# atmel-atmega328p-led-strip-controller.net
KiCad netlist of a schematic drawn in EAGLE
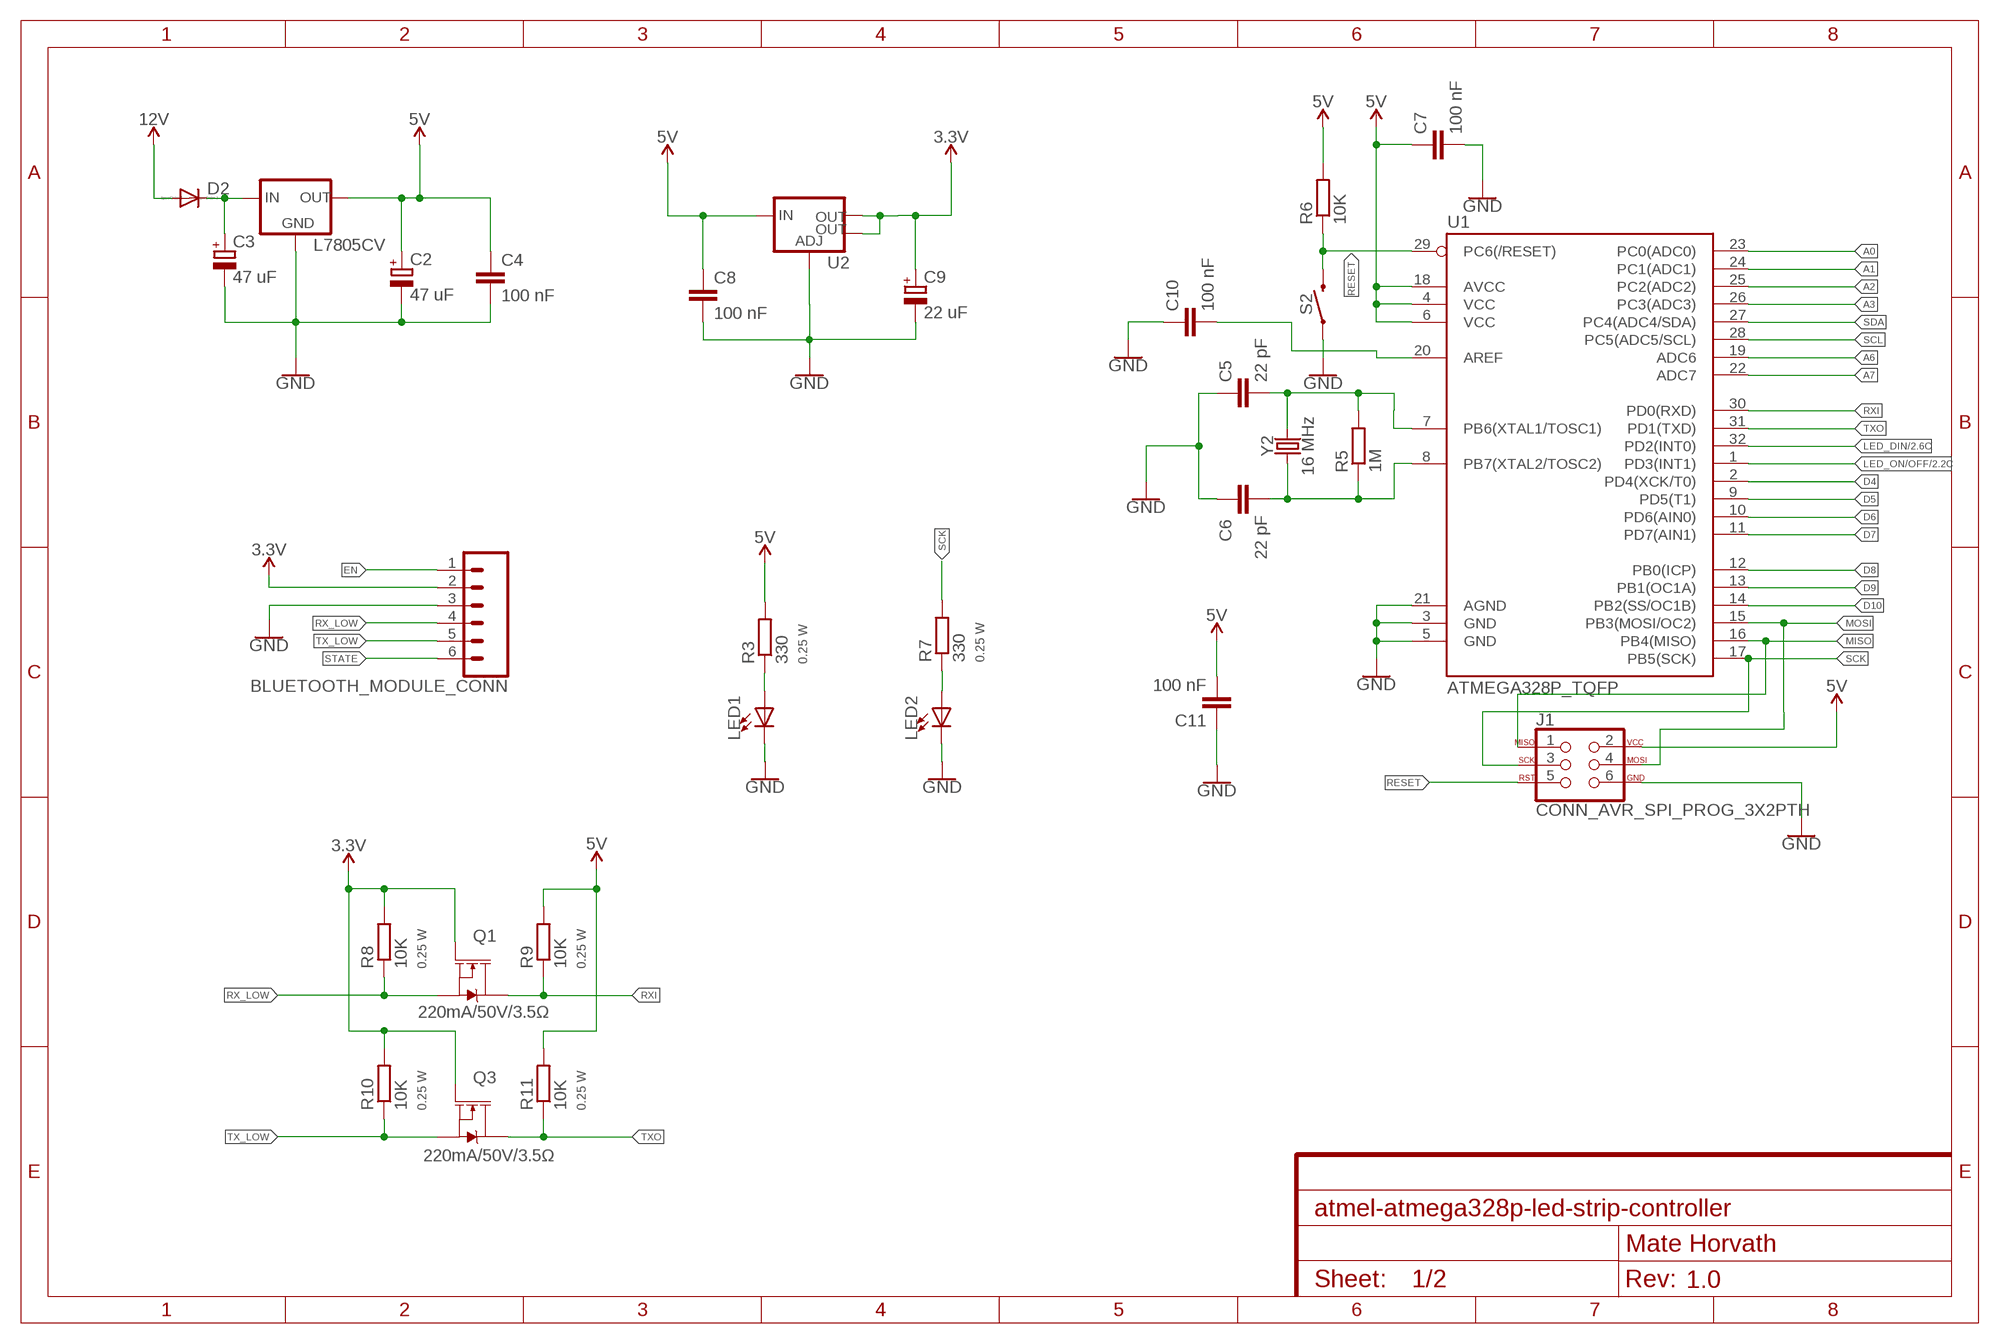
[diagram p0: schematic, sheet 1]
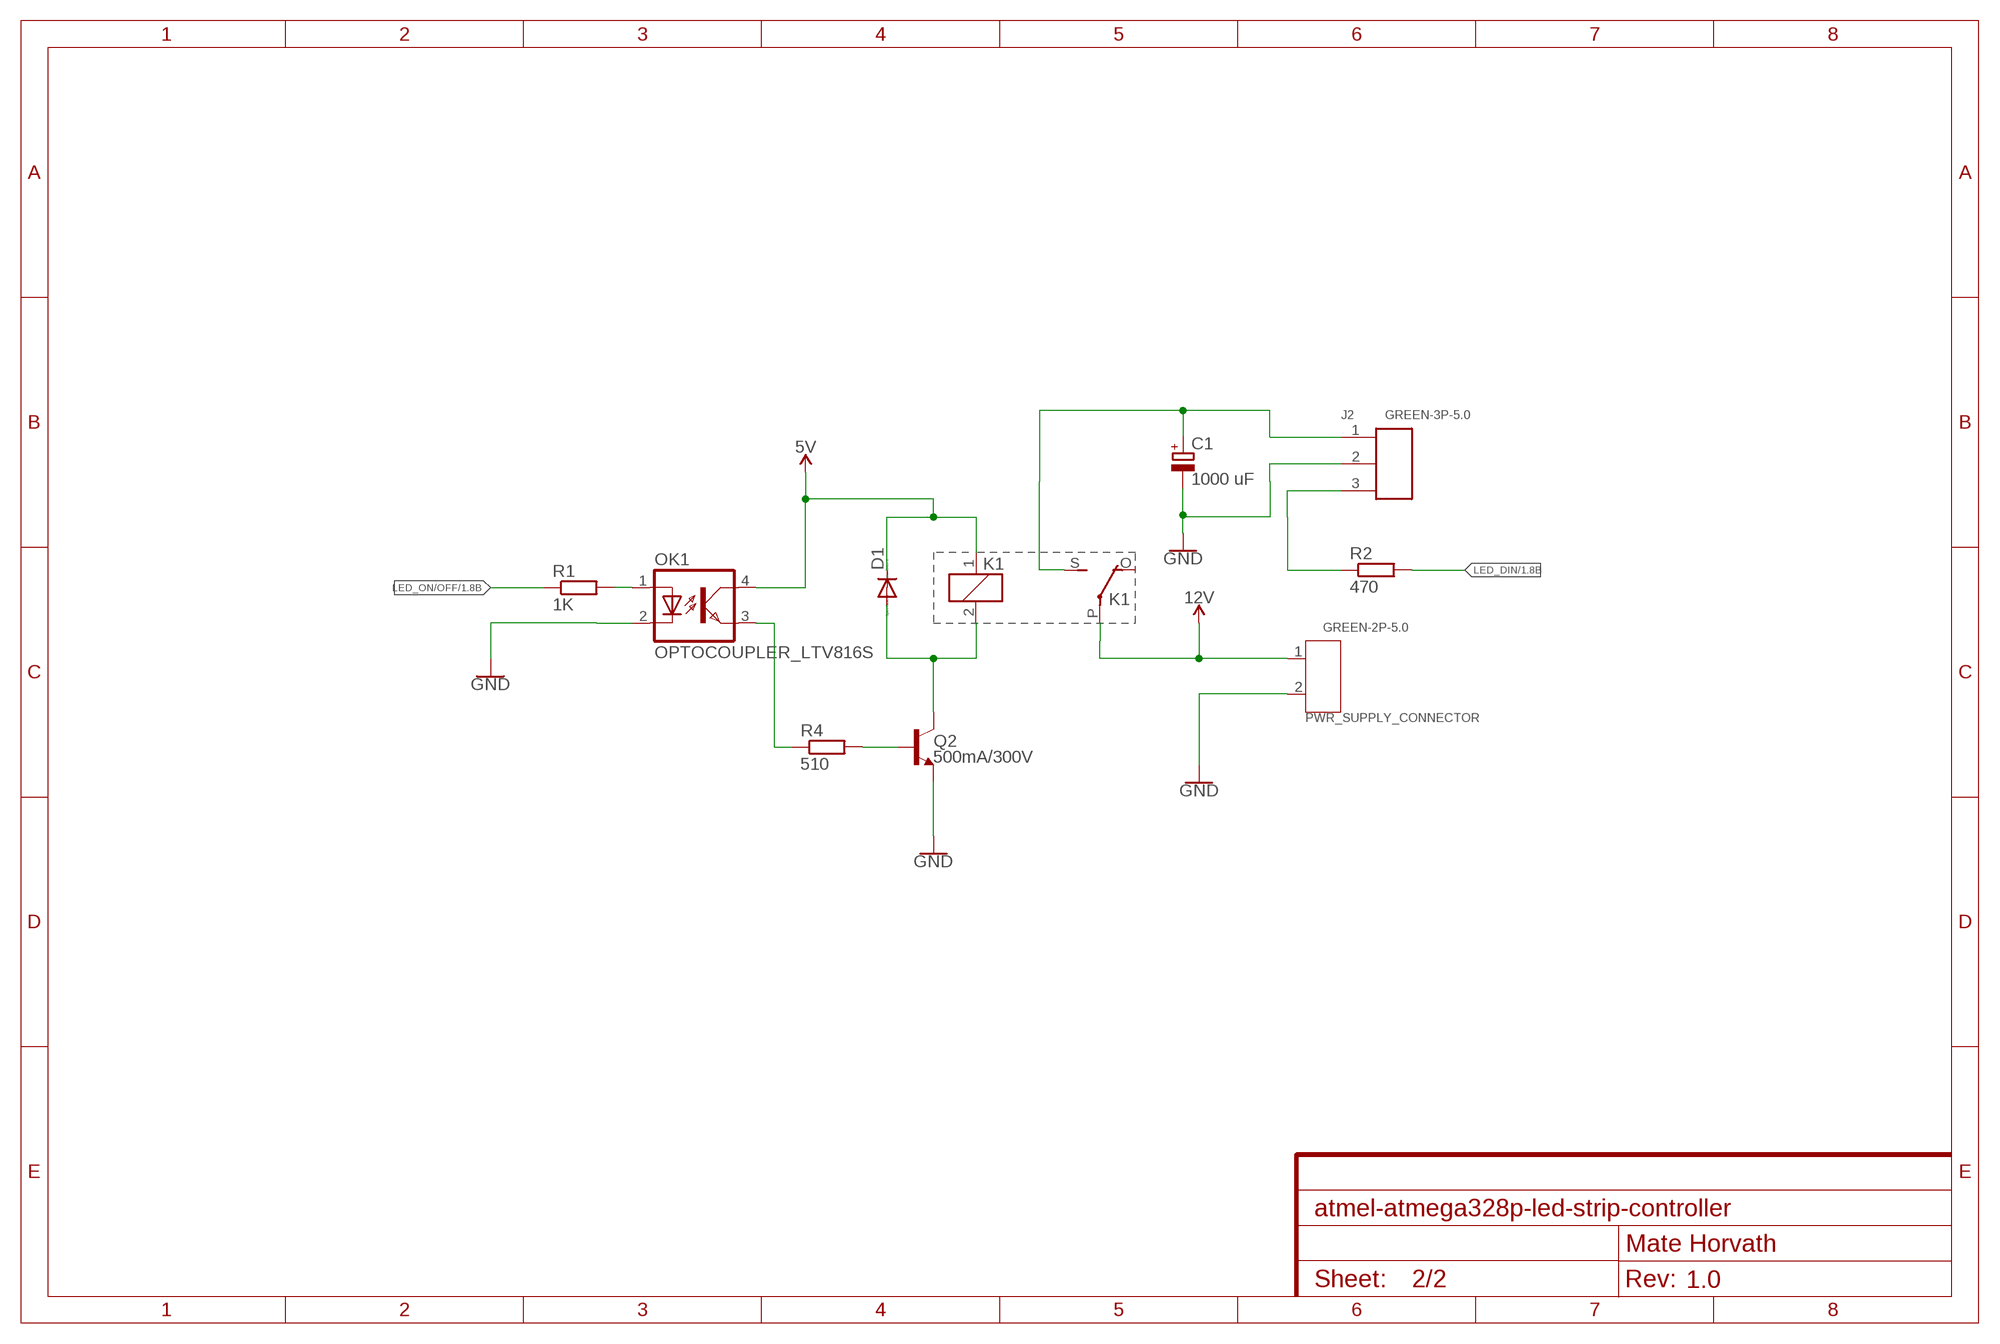
[diagram p1: schematic, sheet 2]

(export (version "E")
  (design (tool "Eeschema 10.0.6"))
  (components
    (comp (ref "C1")
      (value "1000 uF")
      (footprint "eagle-import:E5-13")
      (libsource (lib "eagle-import") (part "CAPACITOR_POLARIZEDE5-13"))
    )
    (comp (ref "D1")
      (value "DIODED-10")
      (footprint "eagle-import:D-10")
      (libsource (lib "eagle-import") (part "DIODED-10"))
    )
    (comp (ref "J2")
      (value "GREEN-3P-5.0")
      (footprint "eagle-import:H3-5.0-15.5X8.0MM")
      (libsource (lib "eagle-import") (part "SCREW-TERMINAL-GREEN(3P-5.0)"))
    )
    (comp (ref "K1")
      (value "RELAY_ZF112")
      (footprint "eagle-import:ZF112")
      (libsource (lib "eagle-import") (part "RELAY_ZF112"))
    )
    (comp (ref "OK1")
      (value "OPTOCOUPLER_LTV816S")
      (footprint "eagle-import:DIL4-SMD")
      (libsource (lib "eagle-import") (part "OPTOCOUPLER_LTV816S"))
    )
    (comp (ref "PWR_SUPPLY_CONNECTOR")
      (value "GREEN-2P-5.0")
      (footprint "eagle-import:H2-5.0-10.5X8.0MM")
      (libsource (lib "eagle-import") (part "SCREW-TERMINAL-GREEN(2P-5.0)"))
    )
    (comp (ref "Q2")
      (value "500mA/300V")
      (footprint "eagle-import:SOT23-3")
      (libsource (lib "eagle-import") (part "TRAN_NPN-MMBTA42"))
    )
    (comp (ref "R1")
      (value "1K")
      (footprint "eagle-import:R1206")
      (fields (field (name "POWER") "0.25 W"))
      (libsource (lib "eagle-import") (part "RESISTORR1206"))
    )
    (comp (ref "R2")
      (value "470")
      (footprint "eagle-import:R1206")
      (fields (field (name "POWER") "0.25 W"))
      (libsource (lib "eagle-import") (part "RESISTORR1206"))
    )
    (comp (ref "R4")
      (value "510")
      (footprint "eagle-import:R1206")
      (fields (field (name "POWER") "0.25 W"))
      (libsource (lib "eagle-import") (part "RESISTORR1206"))
    )
    (comp (ref "BLUETOOTH_MODULE_CONN")
      (value "CONN_06SILK_FEMALE_PTH")
      (footprint "eagle-import:1X06")
      (libsource (lib "eagle-import") (part "CONN_06SILK_FEMALE_PTH"))
    )
    (comp (ref "C2")
      (value "47 uF")
      (footprint "eagle-import:E2,5-5")
      (libsource (lib "eagle-import") (part "CAPACITOR_POLARIZEDE2.5-5"))
    )
    (comp (ref "C3")
      (value "47 uF")
      (footprint "eagle-import:E2,5-5")
      (libsource (lib "eagle-import") (part "CAPACITOR_POLARIZEDE2.5-5"))
    )
    (comp (ref "C4")
      (value "100 nF")
      (footprint "eagle-import:C1206I-C3216M")
      (libsource (lib "eagle-import") (part "CAPACITOR_1C1206"))
    )
    (comp (ref "C5")
      (value "22 pF")
      (footprint "eagle-import:C1206I-C3216M")
      (libsource (lib "eagle-import") (part "CAPACITOR_1C1206"))
    )
    (comp (ref "C6")
      (value "22 pF")
      (footprint "eagle-import:C1206I-C3216M")
      (libsource (lib "eagle-import") (part "CAPACITOR_1C1206"))
    )
    (comp (ref "C7")
      (value "100 nF")
      (footprint "eagle-import:C1206I-C3216M")
      (libsource (lib "eagle-import") (part "CAPACITOR_1C1206"))
    )
    (comp (ref "C8")
      (value "100 nF")
      (footprint "eagle-import:C1206I-C3216M")
      (libsource (lib "eagle-import") (part "CAPACITOR_1C1206"))
    )
    (comp (ref "C9")
      (value "22 uF")
      (footprint "eagle-import:153CLV-0505")
      (libsource (lib "eagle-import") (part "CAPACITOR_POLARIZED153CLV-0505"))
    )
    (comp (ref "C10")
      (value "100 nF")
      (footprint "eagle-import:C1206I-C3216M")
      (libsource (lib "eagle-import") (part "CAPACITOR_1C1206"))
    )
    (comp (ref "C11")
      (value "100 nF")
      (footprint "eagle-import:C1206I-C3216M")
      (libsource (lib "eagle-import") (part "CAPACITOR_1C1206"))
    )
    (comp (ref "D2")
      (value "DIODED-10")
      (footprint "eagle-import:D-10")
      (libsource (lib "eagle-import") (part "DIODED-10"))
    )
    (comp (ref "J1")
      (value "CONN_AVR_SPI_PROG_3X2PTH")
      (footprint "eagle-import:2X3_S")
      (libsource (lib "eagle-import") (part "CONN_AVR_SPI_PROG_3X2PTH"))
    )
    (comp (ref "L7805CV")
      (value "V_REG_78XX_STANDING")
      (footprint "eagle-import:78XXS")
      (libsource (lib "eagle-import") (part "V_REG_78XX_STANDING"))
    )
    (comp (ref "LED1")
      (value "LEDCHIPLED_1206_G")
      (footprint "eagle-import:LED_1206_G")
      (libsource (lib "eagle-import") (part "LEDCHIPLED_1206_G"))
    )
    (comp (ref "LED2")
      (value "LEDCHIPLED_1206_G")
      (footprint "eagle-import:LED_1206_G")
      (libsource (lib "eagle-import") (part "LEDCHIPLED_1206_G"))
    )
    (comp (ref "Q1")
      (value "220mA/50V/3.5Ω")
      (footprint "eagle-import:SOT23-3")
      (libsource (lib "eagle-import") (part "MOSFET_NCHN_SMD-BSS138"))
    )
    (comp (ref "Q3")
      (value "220mA/50V/3.5Ω")
      (footprint "eagle-import:SOT23-3")
      (libsource (lib "eagle-import") (part "MOSFET_NCHN_SMD-BSS138"))
    )
    (comp (ref "R3")
      (value "330")
      (footprint "eagle-import:R1206")
      (fields (field (name "POWER") "0.25 W"))
      (libsource (lib "eagle-import") (part "RESISTORR1206"))
    )
    (comp (ref "R5")
      (value "1M")
      (footprint "eagle-import:R1206")
      (fields (field (name "POWER") "0.25 W"))
      (libsource (lib "eagle-import") (part "RESISTORR1206"))
    )
    (comp (ref "R6")
      (value "10K")
      (footprint "eagle-import:R1206")
      (fields (field (name "POWER") "0.25 W"))
      (libsource (lib "eagle-import") (part "RESISTORR1206"))
    )
    (comp (ref "R7")
      (value "330")
      (footprint "eagle-import:R1206")
      (fields (field (name "POWER") "0.25 W"))
      (libsource (lib "eagle-import") (part "RESISTORR1206"))
    )
    (comp (ref "R8")
      (value "10K")
      (footprint "eagle-import:R1206")
      (fields (field (name "POWER") "0.25 W"))
      (libsource (lib "eagle-import") (part "RESISTORR1206"))
    )
    (comp (ref "R9")
      (value "10K")
      (footprint "eagle-import:R1206")
      (fields (field (name "POWER") "0.25 W"))
      (libsource (lib "eagle-import") (part "RESISTORR1206"))
    )
    (comp (ref "R10")
      (value "10K")
      (footprint "eagle-import:R1206")
      (fields (field (name "POWER") "0.25 W"))
      (libsource (lib "eagle-import") (part "RESISTORR1206"))
    )
    (comp (ref "R11")
      (value "10K")
      (footprint "eagle-import:R1206")
      (fields (field (name "POWER") "0.25 W"))
      (libsource (lib "eagle-import") (part "RESISTORR1206"))
    )
    (comp (ref "S2")
      (value "INPUT_MOMENTARY_SWITCH_SPST-SMD-5.2MM")
      (footprint "eagle-import:TACTILE_SWITCH_SMD_5.2MM")
      (libsource (lib "eagle-import") (part "INPUT_MOMENTARY_SWITCH_SPST-SMD-5.2MM"))
    )
    (comp (ref "U1")
      (value "ATMEGA328P_TQFP")
      (footprint "eagle-import:TQFP32-08")
      (libsource (lib "eagle-import") (part "MCU_ATMEGA328P_TQFP"))
    )
    (comp (ref "U2")
      (value "V_REG_LM1117SOT223")
      (footprint "eagle-import:SOT223")
      (libsource (lib "eagle-import") (part "V_REG_LM1117SOT223"))
    )
    (comp (ref "Y2")
      (value "16 MHz")
      (footprint "eagle-import:CRYSTAL-SMD-3.2X2.5MM")
      (libsource (lib "eagle-import") (part "CRYSTALSMD-3.2X2.5"))
    )
  )
  (nets
    (net (code "1") (name "3.3V") (class "Default")
      (node (ref "BLUETOOTH_MODULE_CONN") (pin "2") (pinfunction "2_2") (pintype "passive"))
      (node (ref "C9") (pin "+") (pinfunction "+_+") (pintype "passive"))
      (node (ref "Q1") (pin "1") (pinfunction "G_1") (pintype "bidirectional"))
      (node (ref "Q3") (pin "1") (pinfunction "G_1") (pintype "bidirectional"))
      (node (ref "R10") (pin "2") (pinfunction "2_2") (pintype "passive"))
      (node (ref "R8") (pin "2") (pinfunction "2_2") (pintype "passive"))
      (node (ref "U2") (pin "2") (pinfunction "OUT_2") (pintype "output"))
      (node (ref "U2") (pin "4") (pinfunction "OUT_4") (pintype "output"))
    )
    (net (code "2") (name "5V") (class "Default")
      (node (ref "C11") (pin "2") (pinfunction "2_2") (pintype "passive"))
      (node (ref "C2") (pin "+") (pinfunction "+_+") (pintype "passive"))
      (node (ref "C4") (pin "1") (pinfunction "1_1") (pintype "passive"))
      (node (ref "C7") (pin "1") (pinfunction "1_1") (pintype "passive"))
      (node (ref "C8") (pin "1") (pinfunction "1_1") (pintype "passive"))
      (node (ref "D1") (pin "C") (pinfunction "C_C") (pintype "passive"))
      (node (ref "J1") (pin "2") (pinfunction "2_2") (pintype "passive"))
      (node (ref "K1") (pin "1") (pinfunction "1_1") (pintype "passive"))
      (node (ref "L7805CV") (pin "OUT") (pinfunction "OUT_OUT") (pintype "passive"))
      (node (ref "OK1") (pin "4") (pinfunction "COL_4") (pintype "passive"))
      (node (ref "R11") (pin "2") (pinfunction "2_2") (pintype "passive"))
      (node (ref "R3") (pin "2") (pinfunction "2_2") (pintype "passive"))
      (node (ref "R6") (pin "2") (pinfunction "2_2") (pintype "passive"))
      (node (ref "R9") (pin "2") (pinfunction "2_2") (pintype "passive"))
      (node (ref "U1") (pin "18") (pinfunction "AVCC_18") (pintype "bidirectional"))
      (node (ref "U1") (pin "4") (pinfunction "VCC_4") (pintype "bidirectional"))
      (node (ref "U1") (pin "6") (pinfunction "VCC_6") (pintype "bidirectional"))
      (node (ref "U2") (pin "3") (pinfunction "IN_3") (pintype "input"))
    )
    (net (code "3") (name "12V") (class "Default")
      (node (ref "D2") (pin "A") (pinfunction "A_A") (pintype "passive"))
      (node (ref "K1") (pin "P") (pinfunction "P_P") (pintype "passive"))
      (node (ref "PWR_SUPPLY_CONNECTOR") (pin "1") (pinfunction "1_1") (pintype "bidirectional"))
    )
    (net (code "4") (name "A0") (class "Default")
      (node (ref "U1") (pin "23") (pinfunction "PC0(ADC0)_23") (pintype "bidirectional"))
    )
    (net (code "5") (name "A1") (class "Default")
      (node (ref "U1") (pin "24") (pinfunction "PC1(ADC1)_24") (pintype "bidirectional"))
    )
    (net (code "6") (name "A2") (class "Default")
      (node (ref "U1") (pin "25") (pinfunction "PC2(ADC2)_25") (pintype "bidirectional"))
    )
    (net (code "7") (name "A3") (class "Default")
      (node (ref "U1") (pin "26") (pinfunction "PC3(ADC3)_26") (pintype "bidirectional"))
    )
    (net (code "8") (name "A6") (class "Default")
      (node (ref "U1") (pin "19") (pinfunction "ADC6_19") (pintype "bidirectional"))
    )
    (net (code "9") (name "A7") (class "Default")
      (node (ref "U1") (pin "22") (pinfunction "ADC7_22") (pintype "bidirectional"))
    )
    (net (code "10") (name "D4") (class "Default")
      (node (ref "U1") (pin "2") (pinfunction "PD4(XCK/T0)_2") (pintype "bidirectional"))
    )
    (net (code "11") (name "D5") (class "Default")
      (node (ref "U1") (pin "9") (pinfunction "PD5(T1)_9") (pintype "bidirectional"))
    )
    (net (code "12") (name "D6") (class "Default")
      (node (ref "U1") (pin "10") (pinfunction "PD6(AIN0)_10") (pintype "bidirectional"))
    )
    (net (code "13") (name "D7") (class "Default")
      (node (ref "U1") (pin "11") (pinfunction "PD7(AIN1)_11") (pintype "bidirectional"))
    )
    (net (code "14") (name "D8") (class "Default")
      (node (ref "U1") (pin "12") (pinfunction "PB0(ICP)_12") (pintype "bidirectional"))
    )
    (net (code "15") (name "D9") (class "Default")
      (node (ref "U1") (pin "13") (pinfunction "PB1(OC1A)_13") (pintype "bidirectional"))
    )
    (net (code "16") (name "D10") (class "Default")
      (node (ref "U1") (pin "14") (pinfunction "PB2(SS/OC1B)_14") (pintype "bidirectional"))
    )
    (net (code "17") (name "EN") (class "Default")
      (node (ref "BLUETOOTH_MODULE_CONN") (pin "1") (pinfunction "1_1") (pintype "passive"))
    )
    (net (code "18") (name "GND") (class "Default")
      (node (ref "BLUETOOTH_MODULE_CONN") (pin "3") (pinfunction "3_3") (pintype "passive"))
      (node (ref "C1") (pin "-") (pinfunction "-_-") (pintype "passive"))
      (node (ref "C10") (pin "1") (pinfunction "1_1") (pintype "passive"))
      (node (ref "C11") (pin "1") (pinfunction "1_1") (pintype "passive"))
      (node (ref "C2") (pin "-") (pinfunction "-_-") (pintype "passive"))
      (node (ref "C3") (pin "-") (pinfunction "-_-") (pintype "passive"))
      (node (ref "C4") (pin "2") (pinfunction "2_2") (pintype "passive"))
      (node (ref "C5") (pin "1") (pinfunction "1_1") (pintype "passive"))
      (node (ref "C6") (pin "1") (pinfunction "1_1") (pintype "passive"))
      (node (ref "C7") (pin "2") (pinfunction "2_2") (pintype "passive"))
      (node (ref "C8") (pin "2") (pinfunction "2_2") (pintype "passive"))
      (node (ref "C9") (pin "-") (pinfunction "-_-") (pintype "passive"))
      (node (ref "J1") (pin "6") (pinfunction "6_6") (pintype "passive"))
      (node (ref "J2") (pin "2") (pinfunction "P$2_2") (pintype "bidirectional"))
      (node (ref "L7805CV") (pin "GND") (pinfunction "GND_GND") (pintype "input"))
      (node (ref "LED1") (pin "C") (pinfunction "C_C") (pintype "passive"))
      (node (ref "LED2") (pin "C") (pinfunction "C_C") (pintype "passive"))
      (node (ref "OK1") (pin "2") (pinfunction "C_2") (pintype "passive"))
      (node (ref "PWR_SUPPLY_CONNECTOR") (pin "2") (pinfunction "2_2") (pintype "bidirectional"))
      (node (ref "Q2") (pin "2") (pinfunction "E_2") (pintype "passive"))
      (node (ref "S2") (pin "1") (pinfunction "1_1") (pintype "passive"))
      (node (ref "U1") (pin "21") (pinfunction "AGND_21") (pintype "bidirectional"))
      (node (ref "U1") (pin "3") (pinfunction "GND_3") (pintype "bidirectional"))
      (node (ref "U1") (pin "5") (pinfunction "GND_5") (pintype "bidirectional"))
      (node (ref "U2") (pin "1") (pinfunction "ADJ_1") (pintype "input"))
    )
    (net (code "19") (name "LED_DIN") (class "Default")
      (node (ref "R2") (pin "2") (pinfunction "2_2") (pintype "passive"))
      (node (ref "U1") (pin "32") (pinfunction "PD2(INT0)_32") (pintype "bidirectional"))
    )
    (net (code "20") (name "LED_ON{slash}OFF") (class "Default")
      (node (ref "R1") (pin "1") (pinfunction "1_1") (pintype "passive"))
      (node (ref "U1") (pin "1") (pinfunction "PD3(INT1)_1") (pintype "bidirectional"))
    )
    (net (code "21") (name "MISO") (class "Default")
      (node (ref "J1") (pin "1") (pinfunction "1_1") (pintype "passive"))
      (node (ref "U1") (pin "16") (pinfunction "PB4(MISO)_16") (pintype "bidirectional"))
    )
    (net (code "22") (name "MOSI") (class "Default")
      (node (ref "J1") (pin "4") (pinfunction "4_4") (pintype "passive"))
      (node (ref "U1") (pin "15") (pinfunction "PB3(MOSI/OC2)_15") (pintype "bidirectional"))
    )
    (net (code "23") (name "Net-(C3-Pad+)") (class "Default")
      (node (ref "C3") (pin "+") (pinfunction "+_+") (pintype "passive"))
      (node (ref "D2") (pin "C") (pinfunction "C_C") (pintype "passive"))
      (node (ref "L7805CV") (pin "IN") (pinfunction "IN_IN") (pintype "input"))
    )
    (net (code "24") (name "Net-(J2-P$1)") (class "Default")
      (node (ref "C1") (pin "+") (pinfunction "+_+") (pintype "passive"))
      (node (ref "J2") (pin "1") (pinfunction "P$1_1") (pintype "bidirectional"))
      (node (ref "K1") (pin "S") (pinfunction "S_S") (pintype "passive"))
    )
    (net (code "25") (name "Net-(J2-P$3)") (class "Default")
      (node (ref "J2") (pin "3") (pinfunction "P$3_3") (pintype "bidirectional"))
      (node (ref "R2") (pin "1") (pinfunction "1_1") (pintype "passive"))
    )
    (net (code "26") (name "Net-(LED1-PadA)") (class "Default")
      (node (ref "LED1") (pin "A") (pinfunction "A_A") (pintype "passive"))
      (node (ref "R3") (pin "1") (pinfunction "1_1") (pintype "passive"))
    )
    (net (code "27") (name "Net-(LED2-PadA)") (class "Default")
      (node (ref "LED2") (pin "A") (pinfunction "A_A") (pintype "passive"))
      (node (ref "R7") (pin "1") (pinfunction "1_1") (pintype "passive"))
    )
    (net (code "28") (name "Net-(OK1-A)") (class "Default")
      (node (ref "OK1") (pin "1") (pinfunction "A_1") (pintype "passive"))
      (node (ref "R1") (pin "2") (pinfunction "2_2") (pintype "passive"))
    )
    (net (code "29") (name "Net-(OK1-EMIT)") (class "Default")
      (node (ref "OK1") (pin "3") (pinfunction "EMIT_3") (pintype "passive"))
      (node (ref "R4") (pin "1") (pinfunction "1_1") (pintype "passive"))
    )
    (net (code "30") (name "Net-(Q2-B)") (class "Default")
      (node (ref "Q2") (pin "1") (pinfunction "B_1") (pintype "passive"))
      (node (ref "R4") (pin "2") (pinfunction "2_2") (pintype "passive"))
    )
    (net (code "31") (name "Net-(Q2-C)") (class "Default")
      (node (ref "D1") (pin "A") (pinfunction "A_A") (pintype "passive"))
      (node (ref "K1") (pin "2") (pinfunction "2_2") (pintype "passive"))
      (node (ref "Q2") (pin "3") (pinfunction "C_3") (pintype "passive"))
    )
    (net (code "32") (name "Net-(U1-AREF)") (class "Default")
      (node (ref "C10") (pin "2") (pinfunction "2_2") (pintype "passive"))
      (node (ref "U1") (pin "20") (pinfunction "AREF_20") (pintype "bidirectional"))
    )
    (net (code "33") (name "Net-(U1-PB6(XTAL1{slash}TOSC1))") (class "Default")
      (node (ref "C5") (pin "2") (pinfunction "2_2") (pintype "passive"))
      (node (ref "R5") (pin "2") (pinfunction "2_2") (pintype "passive"))
      (node (ref "U1") (pin "7") (pinfunction "PB6(XTAL1/TOSC1)_7") (pintype "bidirectional"))
      (node (ref "Y2") (pin "3") (pinfunction "2_3") (pintype "passive"))
    )
    (net (code "34") (name "Net-(U1-PB7(XTAL2{slash}TOSC2))") (class "Default")
      (node (ref "C6") (pin "2") (pinfunction "2_2") (pintype "passive"))
      (node (ref "R5") (pin "1") (pinfunction "1_1") (pintype "passive"))
      (node (ref "U1") (pin "8") (pinfunction "PB7(XTAL2/TOSC2)_8") (pintype "bidirectional"))
      (node (ref "Y2") (pin "1") (pinfunction "1_1") (pintype "passive"))
    )
    (net (code "35") (name "RESET") (class "Default")
      (node (ref "J1") (pin "5") (pinfunction "5_5") (pintype "passive"))
      (node (ref "R6") (pin "1") (pinfunction "1_1") (pintype "passive"))
      (node (ref "S2") (pin "3") (pinfunction "2_3") (pintype "passive"))
      (node (ref "U1") (pin "29") (pinfunction "PC6(/RESET)_29") (pintype "bidirectional"))
    )
    (net (code "36") (name "RXI") (class "Default")
      (node (ref "Q1") (pin "3") (pinfunction "D_3") (pintype "bidirectional"))
      (node (ref "R9") (pin "1") (pinfunction "1_1") (pintype "passive"))
      (node (ref "U1") (pin "30") (pinfunction "PD0(RXD)_30") (pintype "bidirectional"))
    )
    (net (code "37") (name "RX_LOW") (class "Default")
      (node (ref "BLUETOOTH_MODULE_CONN") (pin "4") (pinfunction "4_4") (pintype "passive"))
      (node (ref "Q1") (pin "2") (pinfunction "S_2") (pintype "bidirectional"))
      (node (ref "R8") (pin "1") (pinfunction "1_1") (pintype "passive"))
    )
    (net (code "38") (name "SCK") (class "Default")
      (node (ref "J1") (pin "3") (pinfunction "3_3") (pintype "passive"))
      (node (ref "R7") (pin "2") (pinfunction "2_2") (pintype "passive"))
      (node (ref "U1") (pin "17") (pinfunction "PB5(SCK)_17") (pintype "bidirectional"))
    )
    (net (code "39") (name "SCL") (class "Default")
      (node (ref "U1") (pin "28") (pinfunction "PC5(ADC5/SCL)_28") (pintype "bidirectional"))
    )
    (net (code "40") (name "SDA") (class "Default")
      (node (ref "U1") (pin "27") (pinfunction "PC4(ADC4/SDA)_27") (pintype "bidirectional"))
    )
    (net (code "41") (name "STATE") (class "Default")
      (node (ref "BLUETOOTH_MODULE_CONN") (pin "6") (pinfunction "6_6") (pintype "passive"))
    )
    (net (code "42") (name "TXO") (class "Default")
      (node (ref "Q3") (pin "3") (pinfunction "D_3") (pintype "bidirectional"))
      (node (ref "R11") (pin "1") (pinfunction "1_1") (pintype "passive"))
      (node (ref "U1") (pin "31") (pinfunction "PD1(TXD)_31") (pintype "bidirectional"))
    )
    (net (code "43") (name "TX_LOW") (class "Default")
      (node (ref "BLUETOOTH_MODULE_CONN") (pin "5") (pinfunction "5_5") (pintype "passive"))
      (node (ref "Q3") (pin "2") (pinfunction "S_2") (pintype "bidirectional"))
      (node (ref "R10") (pin "1") (pinfunction "1_1") (pintype "passive"))
    )
    (net (code "44") (name "unconnected-(K1-PadO)") (class "Default")
      (node (ref "K1") (pin "O") (pinfunction "O_O") (pintype "passive"))
    )
  )
)
